# LED.net
KiCad netlist of a schematic drawn in Altium Designer
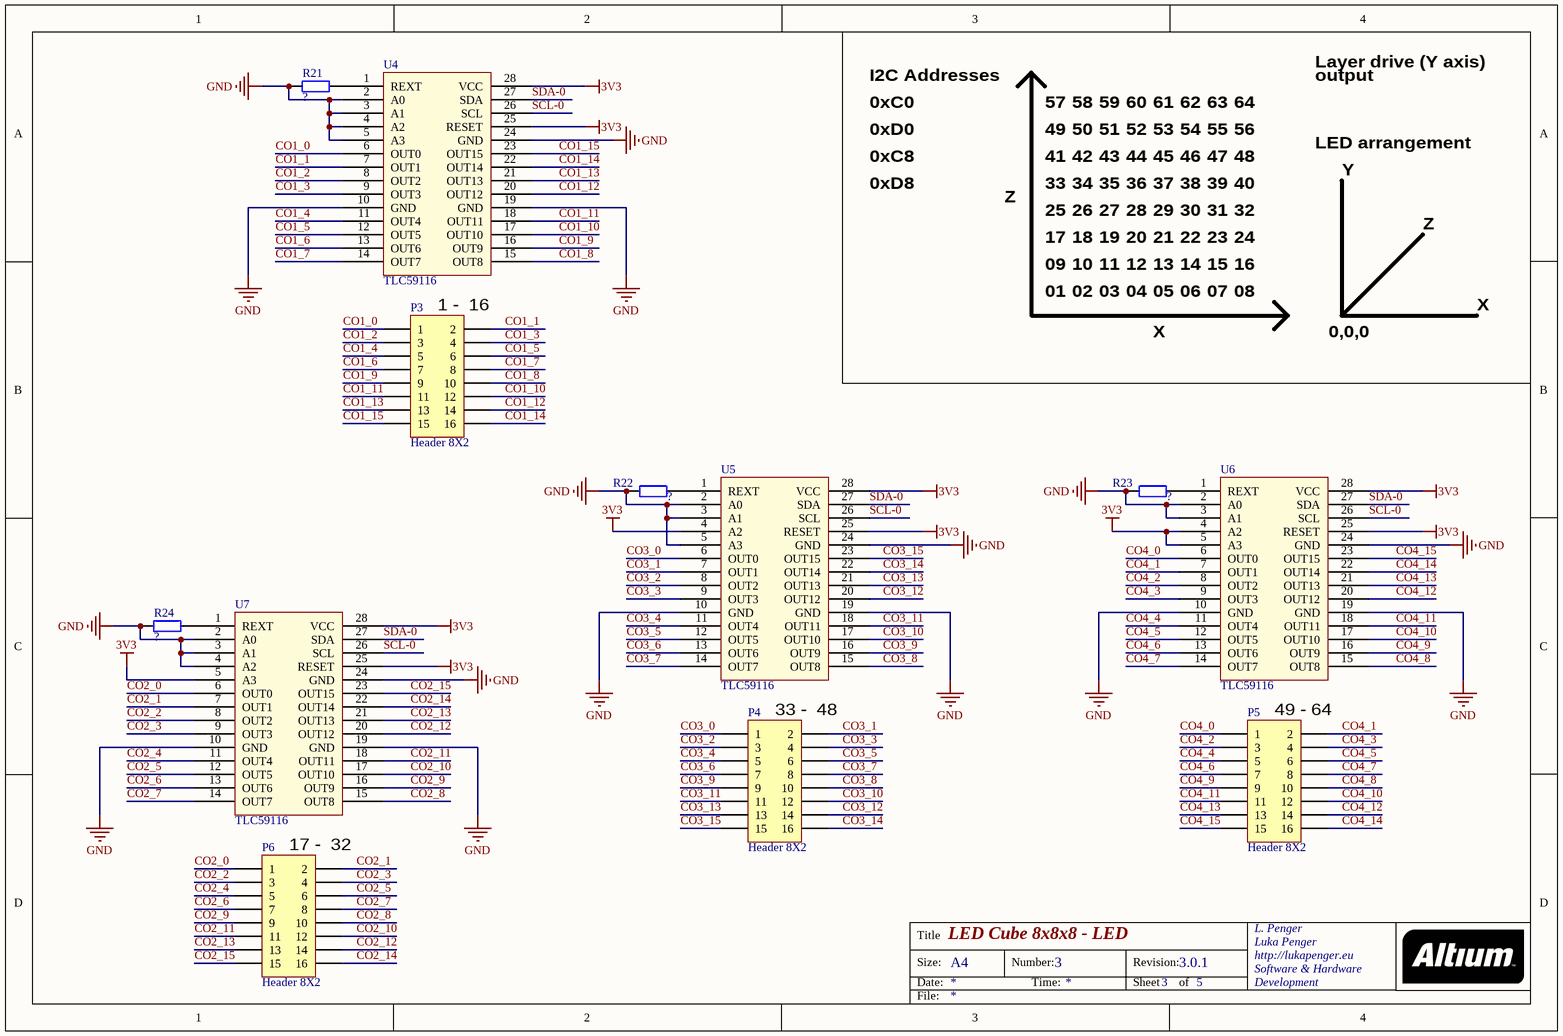
[diagram p0: LED.SchDoc]

(export (version "E")
  (design (tool "Eeschema 10.0.6"))
  (components
    (comp (ref "P3")
      (value "Header 8X2")
      (footprint "IDC-2x8")
      (description "Header, 8-Pin, Dual row")
      (fields (field (name "PUBLISHER") "Altium Limited"))
      (libsource (lib "Miscellaneous Connectors") (part "Header 8X2"))
    )
    (comp (ref "P4")
      (value "Header 8X2")
      (footprint "IDC-2x8")
      (description "Header, 8-Pin, Dual row")
      (fields (field (name "PUBLISHER") "Altium Limited"))
      (libsource (lib "Miscellaneous Connectors") (part "Header 8X2"))
    )
    (comp (ref "P5")
      (value "Header 8X2")
      (footprint "IDC-2x8")
      (description "Header, 8-Pin, Dual row")
      (fields (field (name "PUBLISHER") "Altium Limited"))
      (libsource (lib "Miscellaneous Connectors") (part "Header 8X2"))
    )
    (comp (ref "P6")
      (value "Header 8X2")
      (footprint "IDC-2x8")
      (description "Header, 8-Pin, Dual row")
      (fields (field (name "PUBLISHER") "Altium Limited"))
      (libsource (lib "Miscellaneous Connectors") (part "Header 8X2"))
    )
    (comp (ref "R21")
      (value "?")
      (footprint "1608[0603]")
      (description "Resistor")
      (fields (field (name "PUBLISHER") "Altium Limited"))
      (libsource (lib "") (part "Res2_1"))
    )
    (comp (ref "R22")
      (value "?")
      (footprint "1608[0603]")
      (description "Resistor")
      (fields (field (name "PUBLISHER") "Altium Limited"))
      (libsource (lib "Miscellaneous Devices") (part "Res2"))
    )
    (comp (ref "R23")
      (value "?")
      (footprint "1608[0603]")
      (description "Resistor")
      (fields (field (name "PUBLISHER") "Altium Limited"))
      (libsource (lib "Miscellaneous Devices") (part "Res2"))
    )
    (comp (ref "R24")
      (value "?")
      (footprint "1608[0603]")
      (description "Resistor")
      (fields (field (name "PUBLISHER") "Altium Limited"))
      (libsource (lib "") (part "Res2_1"))
    )
    (comp (ref "U4")
      (value "TLC59116")
      (footprint "TSSOP28")
      (description "16-Channel i2c LED driver")
      (libsource (lib "LukaLIBRARY") (part "TLC59116"))
    )
    (comp (ref "U5")
      (value "TLC59116")
      (footprint "TSSOP28")
      (description "16-Channel i2c LED driver")
      (libsource (lib "LukaLIBRARY") (part "TLC59116"))
    )
    (comp (ref "U6")
      (value "TLC59116")
      (footprint "TSSOP28")
      (description "16-Channel i2c LED driver")
      (libsource (lib "LukaLIBRARY") (part "TLC59116"))
    )
    (comp (ref "U7")
      (value "TLC59116")
      (footprint "TSSOP28")
      (description "16-Channel i2c LED driver")
      (libsource (lib "LukaLIBRARY") (part "TLC59116"))
    )
  )
  (nets
    (net (code "1") (name "/CO1_0") (class "Default")
      (node (ref "P3") (pin "1") (pinfunction "1_1") (pintype "passive"))
      (node (ref "U4") (pin "6") (pinfunction "OUT0_6") (pintype "passive"))
    )
    (net (code "2") (name "/CO1_1") (class "Default")
      (node (ref "P3") (pin "2") (pinfunction "2_2") (pintype "passive"))
      (node (ref "U4") (pin "7") (pinfunction "OUT1_7") (pintype "passive"))
    )
    (net (code "3") (name "/CO1_2") (class "Default")
      (node (ref "P3") (pin "3") (pinfunction "3_3") (pintype "passive"))
      (node (ref "U4") (pin "8") (pinfunction "OUT2_8") (pintype "passive"))
    )
    (net (code "4") (name "/CO1_3") (class "Default")
      (node (ref "P3") (pin "4") (pinfunction "4_4") (pintype "passive"))
      (node (ref "U4") (pin "9") (pinfunction "OUT3_9") (pintype "passive"))
    )
    (net (code "5") (name "/CO1_4") (class "Default")
      (node (ref "P3") (pin "5") (pinfunction "5_5") (pintype "passive"))
      (node (ref "U4") (pin "11") (pinfunction "OUT4_11") (pintype "passive"))
    )
    (net (code "6") (name "/CO1_5") (class "Default")
      (node (ref "P3") (pin "6") (pinfunction "6_6") (pintype "passive"))
      (node (ref "U4") (pin "12") (pinfunction "OUT5_12") (pintype "passive"))
    )
    (net (code "7") (name "/CO1_6") (class "Default")
      (node (ref "P3") (pin "7") (pinfunction "7_7") (pintype "passive"))
      (node (ref "U4") (pin "13") (pinfunction "OUT6_13") (pintype "passive"))
    )
    (net (code "8") (name "/CO1_7") (class "Default")
      (node (ref "P3") (pin "8") (pinfunction "8_8") (pintype "passive"))
      (node (ref "U4") (pin "14") (pinfunction "OUT7_14") (pintype "passive"))
    )
    (net (code "9") (name "/CO1_8") (class "Default")
      (node (ref "P3") (pin "10") (pinfunction "10_10") (pintype "passive"))
      (node (ref "U4") (pin "15") (pinfunction "OUT8_15") (pintype "passive"))
    )
    (net (code "10") (name "/CO1_9") (class "Default")
      (node (ref "P3") (pin "9") (pinfunction "9_9") (pintype "passive"))
      (node (ref "U4") (pin "16") (pinfunction "OUT9_16") (pintype "passive"))
    )
    (net (code "11") (name "/CO1_10") (class "Default")
      (node (ref "P3") (pin "12") (pinfunction "12_12") (pintype "passive"))
      (node (ref "U4") (pin "17") (pinfunction "OUT10_17") (pintype "passive"))
    )
    (net (code "12") (name "/CO1_11") (class "Default")
      (node (ref "P3") (pin "11") (pinfunction "11_11") (pintype "passive"))
      (node (ref "U4") (pin "18") (pinfunction "OUT11_18") (pintype "passive"))
    )
    (net (code "13") (name "/CO1_12") (class "Default")
      (node (ref "P3") (pin "14") (pinfunction "14_14") (pintype "passive"))
      (node (ref "U4") (pin "20") (pinfunction "OUT12_20") (pintype "passive"))
    )
    (net (code "14") (name "/CO1_13") (class "Default")
      (node (ref "P3") (pin "13") (pinfunction "13_13") (pintype "passive"))
      (node (ref "U4") (pin "21") (pinfunction "OUT13_21") (pintype "passive"))
    )
    (net (code "15") (name "/CO1_14") (class "Default")
      (node (ref "P3") (pin "16") (pinfunction "16_16") (pintype "passive"))
      (node (ref "U4") (pin "22") (pinfunction "OUT14_22") (pintype "passive"))
    )
    (net (code "16") (name "/CO1_15") (class "Default")
      (node (ref "P3") (pin "15") (pinfunction "15_15") (pintype "passive"))
      (node (ref "U4") (pin "23") (pinfunction "OUT15_23") (pintype "passive"))
    )
    (net (code "17") (name "/CO2_0") (class "Default")
      (node (ref "P6") (pin "1") (pinfunction "1_1") (pintype "passive"))
      (node (ref "U7") (pin "6") (pinfunction "OUT0_6") (pintype "passive"))
    )
    (net (code "18") (name "/CO2_1") (class "Default")
      (node (ref "P6") (pin "2") (pinfunction "2_2") (pintype "passive"))
      (node (ref "U7") (pin "7") (pinfunction "OUT1_7") (pintype "passive"))
    )
    (net (code "19") (name "/CO2_2") (class "Default")
      (node (ref "P6") (pin "3") (pinfunction "3_3") (pintype "passive"))
      (node (ref "U7") (pin "8") (pinfunction "OUT2_8") (pintype "passive"))
    )
    (net (code "20") (name "/CO2_3") (class "Default")
      (node (ref "P6") (pin "4") (pinfunction "4_4") (pintype "passive"))
      (node (ref "U7") (pin "9") (pinfunction "OUT3_9") (pintype "passive"))
    )
    (net (code "21") (name "/CO2_4") (class "Default")
      (node (ref "P6") (pin "5") (pinfunction "5_5") (pintype "passive"))
      (node (ref "U7") (pin "11") (pinfunction "OUT4_11") (pintype "passive"))
    )
    (net (code "22") (name "/CO2_5") (class "Default")
      (node (ref "P6") (pin "6") (pinfunction "6_6") (pintype "passive"))
      (node (ref "U7") (pin "12") (pinfunction "OUT5_12") (pintype "passive"))
    )
    (net (code "23") (name "/CO2_6") (class "Default")
      (node (ref "P6") (pin "7") (pinfunction "7_7") (pintype "passive"))
      (node (ref "U7") (pin "13") (pinfunction "OUT6_13") (pintype "passive"))
    )
    (net (code "24") (name "/CO2_7") (class "Default")
      (node (ref "P6") (pin "8") (pinfunction "8_8") (pintype "passive"))
      (node (ref "U7") (pin "14") (pinfunction "OUT7_14") (pintype "passive"))
    )
    (net (code "25") (name "/CO2_8") (class "Default")
      (node (ref "P6") (pin "10") (pinfunction "10_10") (pintype "passive"))
      (node (ref "U7") (pin "15") (pinfunction "OUT8_15") (pintype "passive"))
    )
    (net (code "26") (name "/CO2_9") (class "Default")
      (node (ref "P6") (pin "9") (pinfunction "9_9") (pintype "passive"))
      (node (ref "U7") (pin "16") (pinfunction "OUT9_16") (pintype "passive"))
    )
    (net (code "27") (name "/CO2_10") (class "Default")
      (node (ref "P6") (pin "12") (pinfunction "12_12") (pintype "passive"))
      (node (ref "U7") (pin "17") (pinfunction "OUT10_17") (pintype "passive"))
    )
    (net (code "28") (name "/CO2_11") (class "Default")
      (node (ref "P6") (pin "11") (pinfunction "11_11") (pintype "passive"))
      (node (ref "U7") (pin "18") (pinfunction "OUT11_18") (pintype "passive"))
    )
    (net (code "29") (name "/CO2_12") (class "Default")
      (node (ref "P6") (pin "14") (pinfunction "14_14") (pintype "passive"))
      (node (ref "U7") (pin "20") (pinfunction "OUT12_20") (pintype "passive"))
    )
    (net (code "30") (name "/CO2_13") (class "Default")
      (node (ref "P6") (pin "13") (pinfunction "13_13") (pintype "passive"))
      (node (ref "U7") (pin "21") (pinfunction "OUT13_21") (pintype "passive"))
    )
    (net (code "31") (name "/CO2_14") (class "Default")
      (node (ref "P6") (pin "16") (pinfunction "16_16") (pintype "passive"))
      (node (ref "U7") (pin "22") (pinfunction "OUT14_22") (pintype "passive"))
    )
    (net (code "32") (name "/CO2_15") (class "Default")
      (node (ref "P6") (pin "15") (pinfunction "15_15") (pintype "passive"))
      (node (ref "U7") (pin "23") (pinfunction "OUT15_23") (pintype "passive"))
    )
    (net (code "33") (name "/CO3_0") (class "Default")
      (node (ref "P4") (pin "1") (pinfunction "1_1") (pintype "passive"))
      (node (ref "U5") (pin "6") (pinfunction "OUT0_6") (pintype "passive"))
    )
    (net (code "34") (name "/CO3_1") (class "Default")
      (node (ref "P4") (pin "2") (pinfunction "2_2") (pintype "passive"))
      (node (ref "U5") (pin "7") (pinfunction "OUT1_7") (pintype "passive"))
    )
    (net (code "35") (name "/CO3_2") (class "Default")
      (node (ref "P4") (pin "3") (pinfunction "3_3") (pintype "passive"))
      (node (ref "U5") (pin "8") (pinfunction "OUT2_8") (pintype "passive"))
    )
    (net (code "36") (name "/CO3_3") (class "Default")
      (node (ref "P4") (pin "4") (pinfunction "4_4") (pintype "passive"))
      (node (ref "U5") (pin "9") (pinfunction "OUT3_9") (pintype "passive"))
    )
    (net (code "37") (name "/CO3_4") (class "Default")
      (node (ref "P4") (pin "5") (pinfunction "5_5") (pintype "passive"))
      (node (ref "U5") (pin "11") (pinfunction "OUT4_11") (pintype "passive"))
    )
    (net (code "38") (name "/CO3_5") (class "Default")
      (node (ref "P4") (pin "6") (pinfunction "6_6") (pintype "passive"))
      (node (ref "U5") (pin "12") (pinfunction "OUT5_12") (pintype "passive"))
    )
    (net (code "39") (name "/CO3_6") (class "Default")
      (node (ref "P4") (pin "7") (pinfunction "7_7") (pintype "passive"))
      (node (ref "U5") (pin "13") (pinfunction "OUT6_13") (pintype "passive"))
    )
    (net (code "40") (name "/CO3_7") (class "Default")
      (node (ref "P4") (pin "8") (pinfunction "8_8") (pintype "passive"))
      (node (ref "U5") (pin "14") (pinfunction "OUT7_14") (pintype "passive"))
    )
    (net (code "41") (name "/CO3_8") (class "Default")
      (node (ref "P4") (pin "10") (pinfunction "10_10") (pintype "passive"))
      (node (ref "U5") (pin "15") (pinfunction "OUT8_15") (pintype "passive"))
    )
    (net (code "42") (name "/CO3_9") (class "Default")
      (node (ref "P4") (pin "9") (pinfunction "9_9") (pintype "passive"))
      (node (ref "U5") (pin "16") (pinfunction "OUT9_16") (pintype "passive"))
    )
    (net (code "43") (name "/CO3_10") (class "Default")
      (node (ref "P4") (pin "12") (pinfunction "12_12") (pintype "passive"))
      (node (ref "U5") (pin "17") (pinfunction "OUT10_17") (pintype "passive"))
    )
    (net (code "44") (name "/CO3_11") (class "Default")
      (node (ref "P4") (pin "11") (pinfunction "11_11") (pintype "passive"))
      (node (ref "U5") (pin "18") (pinfunction "OUT11_18") (pintype "passive"))
    )
    (net (code "45") (name "/CO3_12") (class "Default")
      (node (ref "P4") (pin "14") (pinfunction "14_14") (pintype "passive"))
      (node (ref "U5") (pin "20") (pinfunction "OUT12_20") (pintype "passive"))
    )
    (net (code "46") (name "/CO3_13") (class "Default")
      (node (ref "P4") (pin "13") (pinfunction "13_13") (pintype "passive"))
      (node (ref "U5") (pin "21") (pinfunction "OUT13_21") (pintype "passive"))
    )
    (net (code "47") (name "/CO3_14") (class "Default")
      (node (ref "P4") (pin "16") (pinfunction "16_16") (pintype "passive"))
      (node (ref "U5") (pin "22") (pinfunction "OUT14_22") (pintype "passive"))
    )
    (net (code "48") (name "/CO3_15") (class "Default")
      (node (ref "P4") (pin "15") (pinfunction "15_15") (pintype "passive"))
      (node (ref "U5") (pin "23") (pinfunction "OUT15_23") (pintype "passive"))
    )
    (net (code "49") (name "/CO4_0") (class "Default")
      (node (ref "P5") (pin "1") (pinfunction "1_1") (pintype "passive"))
      (node (ref "U6") (pin "6") (pinfunction "OUT0_6") (pintype "passive"))
    )
    (net (code "50") (name "/CO4_1") (class "Default")
      (node (ref "P5") (pin "2") (pinfunction "2_2") (pintype "passive"))
      (node (ref "U6") (pin "7") (pinfunction "OUT1_7") (pintype "passive"))
    )
    (net (code "51") (name "/CO4_2") (class "Default")
      (node (ref "P5") (pin "3") (pinfunction "3_3") (pintype "passive"))
      (node (ref "U6") (pin "8") (pinfunction "OUT2_8") (pintype "passive"))
    )
    (net (code "52") (name "/CO4_3") (class "Default")
      (node (ref "P5") (pin "4") (pinfunction "4_4") (pintype "passive"))
      (node (ref "U6") (pin "9") (pinfunction "OUT3_9") (pintype "passive"))
    )
    (net (code "53") (name "/CO4_4") (class "Default")
      (node (ref "P5") (pin "5") (pinfunction "5_5") (pintype "passive"))
      (node (ref "U6") (pin "11") (pinfunction "OUT4_11") (pintype "passive"))
    )
    (net (code "54") (name "/CO4_5") (class "Default")
      (node (ref "P5") (pin "6") (pinfunction "6_6") (pintype "passive"))
      (node (ref "U6") (pin "12") (pinfunction "OUT5_12") (pintype "passive"))
    )
    (net (code "55") (name "/CO4_6") (class "Default")
      (node (ref "P5") (pin "7") (pinfunction "7_7") (pintype "passive"))
      (node (ref "U6") (pin "13") (pinfunction "OUT6_13") (pintype "passive"))
    )
    (net (code "56") (name "/CO4_7") (class "Default")
      (node (ref "P5") (pin "8") (pinfunction "8_8") (pintype "passive"))
      (node (ref "U6") (pin "14") (pinfunction "OUT7_14") (pintype "passive"))
    )
    (net (code "57") (name "/CO4_8") (class "Default")
      (node (ref "P5") (pin "10") (pinfunction "10_10") (pintype "passive"))
      (node (ref "U6") (pin "15") (pinfunction "OUT8_15") (pintype "passive"))
    )
    (net (code "58") (name "/CO4_9") (class "Default")
      (node (ref "P5") (pin "9") (pinfunction "9_9") (pintype "passive"))
      (node (ref "U6") (pin "16") (pinfunction "OUT9_16") (pintype "passive"))
    )
    (net (code "59") (name "/CO4_10") (class "Default")
      (node (ref "P5") (pin "12") (pinfunction "12_12") (pintype "passive"))
      (node (ref "U6") (pin "17") (pinfunction "OUT10_17") (pintype "passive"))
    )
    (net (code "60") (name "/CO4_11") (class "Default")
      (node (ref "P5") (pin "11") (pinfunction "11_11") (pintype "passive"))
      (node (ref "U6") (pin "18") (pinfunction "OUT11_18") (pintype "passive"))
    )
    (net (code "61") (name "/CO4_12") (class "Default")
      (node (ref "P5") (pin "14") (pinfunction "14_14") (pintype "passive"))
      (node (ref "U6") (pin "20") (pinfunction "OUT12_20") (pintype "passive"))
    )
    (net (code "62") (name "/CO4_13") (class "Default")
      (node (ref "P5") (pin "13") (pinfunction "13_13") (pintype "passive"))
      (node (ref "U6") (pin "21") (pinfunction "OUT13_21") (pintype "passive"))
    )
    (net (code "63") (name "/CO4_14") (class "Default")
      (node (ref "P5") (pin "16") (pinfunction "16_16") (pintype "passive"))
      (node (ref "U6") (pin "22") (pinfunction "OUT14_22") (pintype "passive"))
    )
    (net (code "64") (name "/CO4_15") (class "Default")
      (node (ref "P5") (pin "15") (pinfunction "15_15") (pintype "passive"))
      (node (ref "U6") (pin "23") (pinfunction "OUT15_23") (pintype "passive"))
    )
    (net (code "65") (name "/SCL-0") (class "Default")
      (node (ref "U4") (pin "26") (pinfunction "SCL_26") (pintype "passive"))
      (node (ref "U5") (pin "26") (pinfunction "SCL_26") (pintype "passive"))
      (node (ref "U6") (pin "26") (pinfunction "SCL_26") (pintype "passive"))
      (node (ref "U7") (pin "26") (pinfunction "SCL_26") (pintype "passive"))
    )
    (net (code "66") (name "/SDA-0") (class "Default")
      (node (ref "U4") (pin "27") (pinfunction "SDA_27") (pintype "passive"))
      (node (ref "U5") (pin "27") (pinfunction "SDA_27") (pintype "passive"))
      (node (ref "U6") (pin "27") (pinfunction "SDA_27") (pintype "passive"))
      (node (ref "U7") (pin "27") (pinfunction "SDA_27") (pintype "passive"))
    )
    (net (code "67") (name "3V3") (class "Default")
      (node (ref "U4") (pin "25") (pinfunction "RESET_25") (pintype "passive"))
      (node (ref "U4") (pin "28") (pinfunction "VCC_28") (pintype "passive"))
      (node (ref "U5") (pin "25") (pinfunction "RESET_25") (pintype "passive"))
      (node (ref "U5") (pin "28") (pinfunction "VCC_28") (pintype "passive"))
      (node (ref "U5") (pin "4") (pinfunction "A2_4") (pintype "passive"))
      (node (ref "U6") (pin "25") (pinfunction "RESET_25") (pintype "passive"))
      (node (ref "U6") (pin "28") (pinfunction "VCC_28") (pintype "passive"))
      (node (ref "U6") (pin "4") (pinfunction "A2_4") (pintype "passive"))
      (node (ref "U6") (pin "5") (pinfunction "A3_5") (pintype "passive"))
      (node (ref "U7") (pin "25") (pinfunction "RESET_25") (pintype "passive"))
      (node (ref "U7") (pin "28") (pinfunction "VCC_28") (pintype "passive"))
      (node (ref "U7") (pin "5") (pinfunction "A3_5") (pintype "passive"))
    )
    (net (code "68") (name "GND") (class "Default")
      (node (ref "R21") (pin "2") (pinfunction "2_2") (pintype "passive"))
      (node (ref "R22") (pin "1") (pinfunction "1_1") (pintype "passive"))
      (node (ref "R23") (pin "1") (pinfunction "1_1") (pintype "passive"))
      (node (ref "R24") (pin "2") (pinfunction "2_2") (pintype "passive"))
      (node (ref "U4") (pin "10") (pinfunction "GND_10") (pintype "passive"))
      (node (ref "U4") (pin "19") (pinfunction "GND_19") (pintype "passive"))
      (node (ref "U4") (pin "2") (pinfunction "A0_2") (pintype "passive"))
      (node (ref "U4") (pin "24") (pinfunction "GND_24") (pintype "passive"))
      (node (ref "U4") (pin "3") (pinfunction "A1_3") (pintype "passive"))
      (node (ref "U4") (pin "4") (pinfunction "A2_4") (pintype "passive"))
      (node (ref "U4") (pin "5") (pinfunction "A3_5") (pintype "passive"))
      (node (ref "U5") (pin "10") (pinfunction "GND_10") (pintype "passive"))
      (node (ref "U5") (pin "19") (pinfunction "GND_19") (pintype "passive"))
      (node (ref "U5") (pin "2") (pinfunction "A0_2") (pintype "passive"))
      (node (ref "U5") (pin "24") (pinfunction "GND_24") (pintype "passive"))
      (node (ref "U5") (pin "3") (pinfunction "A1_3") (pintype "passive"))
      (node (ref "U5") (pin "5") (pinfunction "A3_5") (pintype "passive"))
      (node (ref "U6") (pin "10") (pinfunction "GND_10") (pintype "passive"))
      (node (ref "U6") (pin "19") (pinfunction "GND_19") (pintype "passive"))
      (node (ref "U6") (pin "2") (pinfunction "A0_2") (pintype "passive"))
      (node (ref "U6") (pin "24") (pinfunction "GND_24") (pintype "passive"))
      (node (ref "U6") (pin "3") (pinfunction "A1_3") (pintype "passive"))
      (node (ref "U7") (pin "10") (pinfunction "GND_10") (pintype "passive"))
      (node (ref "U7") (pin "19") (pinfunction "GND_19") (pintype "passive"))
      (node (ref "U7") (pin "2") (pinfunction "A0_2") (pintype "passive"))
      (node (ref "U7") (pin "24") (pinfunction "GND_24") (pintype "passive"))
      (node (ref "U7") (pin "3") (pinfunction "A1_3") (pintype "passive"))
      (node (ref "U7") (pin "4") (pinfunction "A2_4") (pintype "passive"))
    )
    (net (code "69") (name "Net-(U4-REXT)") (class "Default")
      (node (ref "R21") (pin "1") (pinfunction "1_1") (pintype "passive"))
      (node (ref "U4") (pin "1") (pinfunction "REXT_1") (pintype "passive"))
    )
    (net (code "70") (name "Net-(U5-REXT)") (class "Default")
      (node (ref "R22") (pin "2") (pinfunction "2_2") (pintype "passive"))
      (node (ref "U5") (pin "1") (pinfunction "REXT_1") (pintype "passive"))
    )
    (net (code "71") (name "Net-(U6-REXT)") (class "Default")
      (node (ref "R23") (pin "2") (pinfunction "2_2") (pintype "passive"))
      (node (ref "U6") (pin "1") (pinfunction "REXT_1") (pintype "passive"))
    )
    (net (code "72") (name "Net-(U7-REXT)") (class "Default")
      (node (ref "R24") (pin "1") (pinfunction "1_1") (pintype "passive"))
      (node (ref "U7") (pin "1") (pinfunction "REXT_1") (pintype "passive"))
    )
  )
)
